# led-board.net
KiCad netlist of a schematic drawn in EAGLE
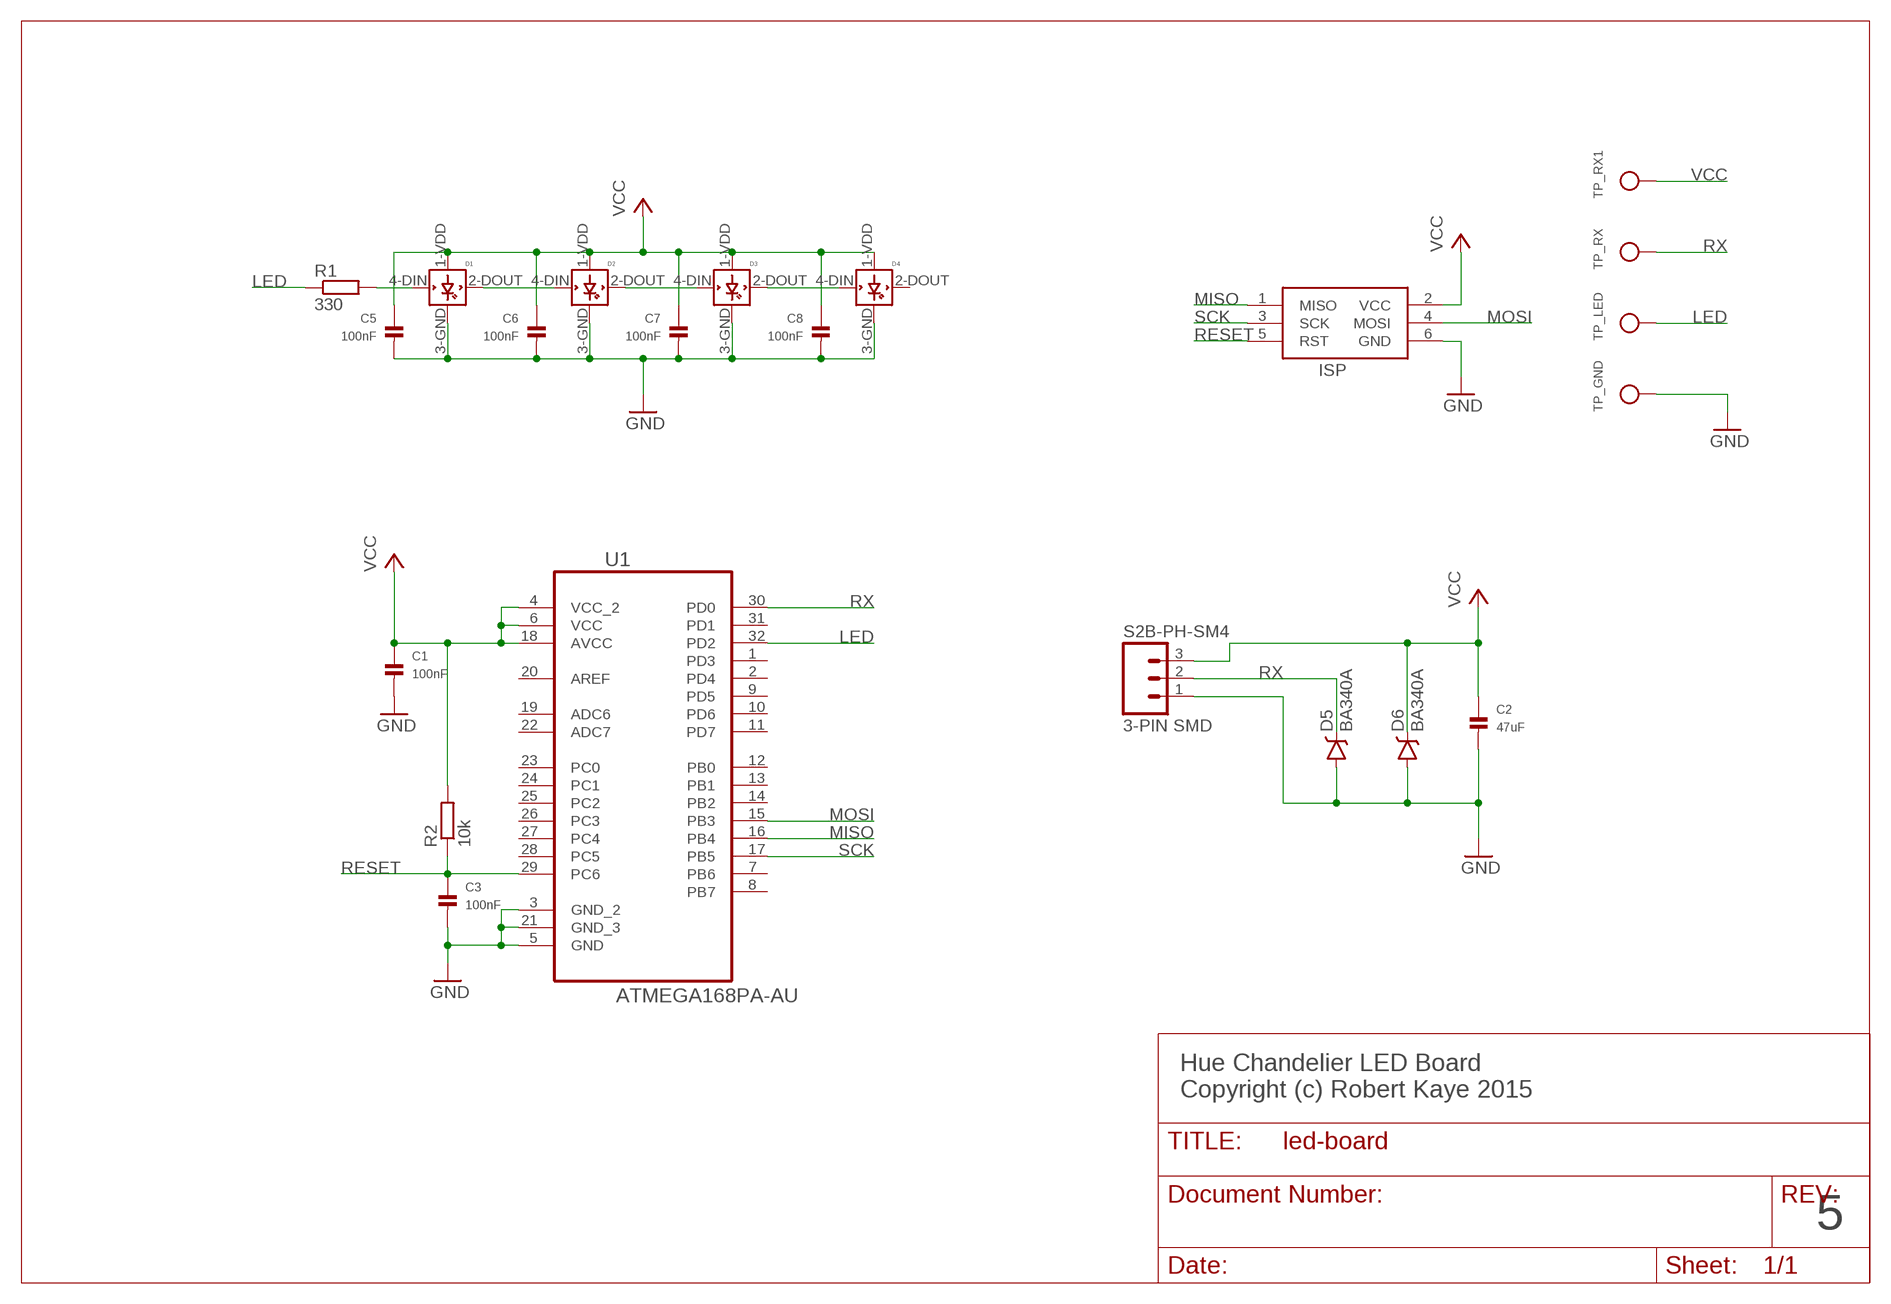
[diagram p0: schematic, sheet 1]

(export (version "E")
  (design (tool "Eeschema 10.0.6"))
  (components
    (comp (ref "C1")
      (value "100nF")
      (footprint "eagle-import:0805")
      (fields (field (name "MPN") "MCSH21B104K250CT"))
      (libsource (lib "eagle-import") (part "CAP_CERAMIC0805"))
    )
    (comp (ref "C2")
      (value "47uF")
      (footprint "eagle-import:1206")
      (fields (field (name "MPN") "CC0805KKX7R7BB105"))
      (libsource (lib "eagle-import") (part "CAP_CERAMIC1206"))
    )
    (comp (ref "C3")
      (value "100nF")
      (footprint "eagle-import:0805")
      (fields (field (name "MPN") "MCSH21B104K250CT"))
      (libsource (lib "eagle-import") (part "CAP_CERAMIC0805"))
    )
    (comp (ref "C5")
      (value "100nF")
      (footprint "eagle-import:0805")
      (fields (field (name "MPN") "MCSH21B104K250CT"))
      (libsource (lib "eagle-import") (part "CAP_CERAMIC0805"))
    )
    (comp (ref "C6")
      (value "100nF")
      (footprint "eagle-import:0805")
      (fields (field (name "MPN") "MCSH21B104K250CT"))
      (libsource (lib "eagle-import") (part "CAP_CERAMIC0805"))
    )
    (comp (ref "C7")
      (value "100nF")
      (footprint "eagle-import:0805")
      (fields (field (name "MPN") "MCSH21B104K250CT"))
      (libsource (lib "eagle-import") (part "CAP_CERAMIC0805"))
    )
    (comp (ref "C8")
      (value "100nF")
      (footprint "eagle-import:0805")
      (fields (field (name "MPN") "MCSH21B104K250CT"))
      (libsource (lib "eagle-import") (part "CAP_CERAMIC0805"))
    )
    (comp (ref "D1")
      (value "WS2812B")
      (footprint "eagle-import:WS2812B")
      (libsource (lib "eagle-import") (part "WS2812B"))
    )
    (comp (ref "D2")
      (value "WS2812B")
      (footprint "eagle-import:WS2812B")
      (libsource (lib "eagle-import") (part "WS2812B"))
    )
    (comp (ref "D3")
      (value "WS2812B")
      (footprint "eagle-import:WS2812B")
      (libsource (lib "eagle-import") (part "WS2812B"))
    )
    (comp (ref "D4")
      (value "WS2812B")
      (footprint "eagle-import:WS2812B")
      (libsource (lib "eagle-import") (part "WS2812B"))
    )
    (comp (ref "D5")
      (value "BA340A")
      (footprint "eagle-import:SMA-DIODE")
      (fields (field (name "MPN") "B330A-13-F"))
      (libsource (lib "eagle-import") (part "B340A"))
    )
    (comp (ref "D6")
      (value "BA340A")
      (footprint "eagle-import:SMA-DIODE")
      (fields (field (name "MPN") "B330A-13-F"))
      (libsource (lib "eagle-import") (part "B340A"))
    )
    (comp (ref "ISP")
      (value "AVRISP-6")
      (footprint "eagle-import:AVRISP")
      (libsource (lib "eagle-import") (part "AVRISP-6"))
    )
    (comp (ref "R1")
      (value "330")
      (footprint "eagle-import:R0805")
      (fields (field (name "MPN") "RC0805JR-07330RL"))
      (libsource (lib "eagle-import") (part "R-EU_R0805"))
    )
    (comp (ref "R2")
      (value "10k")
      (footprint "eagle-import:R0805")
      (fields (field (name "MPN") "RT0805FRE0710KL"))
      (libsource (lib "eagle-import") (part "R-EU_R0805"))
    )
    (comp (ref "S2B-PH-SM4")
      (value "3-PIN SMD")
      (footprint "eagle-import:JST-3-SMD")
      (fields (field (name "MF") "FARNELL") (field (name "MPN") "S3B-PH-SM4-TB(LF)(SN)"))
      (libsource (lib "eagle-import") (part "M03JST-SMD"))
    )
    (comp (ref "TP_GND")
      (value "TESTPOINT1.5X2.0MM_NOCREAM")
      (footprint "eagle-import:PAD-1.5X2.0")
      (libsource (lib "eagle-import") (part "TESTPOINT1.5X2.0MM_NOCREAM"))
    )
    (comp (ref "TP_LED")
      (value "TESTPOINT1.5X2.0MM_NOCREAM")
      (footprint "eagle-import:PAD-1.5X2.0")
      (libsource (lib "eagle-import") (part "TESTPOINT1.5X2.0MM_NOCREAM"))
    )
    (comp (ref "TP_RX")
      (value "TESTPOINT1.5X2.0MM_NOCREAM")
      (footprint "eagle-import:PAD-1.5X2.0")
      (libsource (lib "eagle-import") (part "TESTPOINT1.5X2.0MM_NOCREAM"))
    )
    (comp (ref "TP_RX1")
      (value "TESTPOINT1.5X2.0MM_NOCREAM")
      (footprint "eagle-import:PAD-1.5X2.0")
      (libsource (lib "eagle-import") (part "TESTPOINT1.5X2.0MM_NOCREAM"))
    )
    (comp (ref "U1")
      (value "ATMEGA168PA-AU")
      (footprint "eagle-import:QFP80P900X900X120-32N")
      (fields (field (name "OC_NEWARK") "68T2717"))
      (libsource (lib "eagle-import") (part "ATMEGA168PA-AU"))
    )
  )
  (nets
    (net (code "1") (name "/LED") (class "Default")
      (node (ref "R1") (pin "1") (pinfunction "1_1") (pintype "passive"))
      (node (ref "TP_LED") (pin "P$1") (pinfunction "P$1_P$1") (pintype "bidirectional"))
      (node (ref "U1") (pin "32") (pinfunction "PD2_32") (pintype "bidirectional"))
    )
    (net (code "2") (name "/MISO") (class "Default")
      (node (ref "ISP") (pin "1") (pinfunction "MISO_1") (pintype "input"))
      (node (ref "U1") (pin "16") (pinfunction "PB4_16") (pintype "bidirectional"))
    )
    (net (code "3") (name "/MOSI") (class "Default")
      (node (ref "ISP") (pin "4") (pinfunction "MOSI_4") (pintype "output"))
      (node (ref "U1") (pin "15") (pinfunction "PB3_15") (pintype "bidirectional"))
    )
    (net (code "4") (name "/RESET") (class "Default")
      (node (ref "C3") (pin "1") (pinfunction "P$1_1") (pintype "passive"))
      (node (ref "ISP") (pin "5") (pinfunction "RST_5") (pintype "output"))
      (node (ref "R2") (pin "1") (pinfunction "1_1") (pintype "passive"))
      (node (ref "U1") (pin "29") (pinfunction "PC6_29") (pintype "bidirectional"))
    )
    (net (code "5") (name "/RX") (class "Default")
      (node (ref "D5") (pin "C") (pinfunction "C_C") (pintype "passive"))
      (node (ref "S2B-PH-SM4") (pin "2") (pinfunction "2_2") (pintype "passive"))
      (node (ref "TP_RX") (pin "P$1") (pinfunction "P$1_P$1") (pintype "bidirectional"))
      (node (ref "U1") (pin "30") (pinfunction "PD0_30") (pintype "bidirectional"))
    )
    (net (code "6") (name "/SCK") (class "Default")
      (node (ref "ISP") (pin "3") (pinfunction "SCK_3") (pintype "output"))
      (node (ref "U1") (pin "17") (pinfunction "PB5_17") (pintype "bidirectional"))
    )
    (net (code "7") (name "GND") (class "Default")
      (node (ref "C1") (pin "2") (pinfunction "P$2_2") (pintype "passive"))
      (node (ref "C2") (pin "2") (pinfunction "P$2_2") (pintype "passive"))
      (node (ref "C3") (pin "2") (pinfunction "P$2_2") (pintype "passive"))
      (node (ref "C5") (pin "2") (pinfunction "P$2_2") (pintype "passive"))
      (node (ref "C6") (pin "2") (pinfunction "P$2_2") (pintype "passive"))
      (node (ref "C7") (pin "2") (pinfunction "P$2_2") (pintype "passive"))
      (node (ref "C8") (pin "2") (pinfunction "P$2_2") (pintype "passive"))
      (node (ref "D1") (pin "3-GND") (pinfunction "GND_3-GND") (pintype "bidirectional"))
      (node (ref "D2") (pin "3-GND") (pinfunction "GND_3-GND") (pintype "bidirectional"))
      (node (ref "D3") (pin "3-GND") (pinfunction "GND_3-GND") (pintype "bidirectional"))
      (node (ref "D4") (pin "3-GND") (pinfunction "GND_3-GND") (pintype "bidirectional"))
      (node (ref "D5") (pin "A") (pinfunction "A_A") (pintype "passive"))
      (node (ref "D6") (pin "A") (pinfunction "A_A") (pintype "passive"))
      (node (ref "ISP") (pin "6") (pinfunction "GND_6") (pintype "power_in"))
      (node (ref "S2B-PH-SM4") (pin "1") (pinfunction "1_1") (pintype "passive"))
      (node (ref "TP_GND") (pin "P$1") (pinfunction "P$1_P$1") (pintype "bidirectional"))
      (node (ref "U1") (pin "21") (pinfunction "GND_3_21") (pintype "passive"))
      (node (ref "U1") (pin "3") (pinfunction "GND_2_3") (pintype "passive"))
      (node (ref "U1") (pin "5") (pinfunction "GND_5") (pintype "passive"))
    )
    (net (code "8") (name "Net-(D1-DIN)") (class "Default")
      (node (ref "D1") (pin "4-DIN") (pinfunction "DIN_4-DIN") (pintype "input"))
      (node (ref "R1") (pin "2") (pinfunction "2_2") (pintype "passive"))
    )
    (net (code "9") (name "Net-(D1-DOUT)") (class "Default")
      (node (ref "D1") (pin "2-DOUT") (pinfunction "DOUT_2-DOUT") (pintype "output"))
      (node (ref "D2") (pin "4-DIN") (pinfunction "DIN_4-DIN") (pintype "input"))
    )
    (net (code "10") (name "Net-(D2-DOUT)") (class "Default")
      (node (ref "D2") (pin "2-DOUT") (pinfunction "DOUT_2-DOUT") (pintype "output"))
      (node (ref "D3") (pin "4-DIN") (pinfunction "DIN_4-DIN") (pintype "input"))
    )
    (net (code "11") (name "Net-(D3-DOUT)") (class "Default")
      (node (ref "D3") (pin "2-DOUT") (pinfunction "DOUT_2-DOUT") (pintype "output"))
      (node (ref "D4") (pin "4-DIN") (pinfunction "DIN_4-DIN") (pintype "input"))
    )
    (net (code "12") (name "VCC") (class "Default")
      (node (ref "C1") (pin "1") (pinfunction "P$1_1") (pintype "passive"))
      (node (ref "C2") (pin "1") (pinfunction "P$1_1") (pintype "passive"))
      (node (ref "C5") (pin "1") (pinfunction "P$1_1") (pintype "passive"))
      (node (ref "C6") (pin "1") (pinfunction "P$1_1") (pintype "passive"))
      (node (ref "C7") (pin "1") (pinfunction "P$1_1") (pintype "passive"))
      (node (ref "C8") (pin "1") (pinfunction "P$1_1") (pintype "passive"))
      (node (ref "D1") (pin "1-VDD") (pinfunction "VDD_1-VDD") (pintype "bidirectional"))
      (node (ref "D2") (pin "1-VDD") (pinfunction "VDD_1-VDD") (pintype "bidirectional"))
      (node (ref "D3") (pin "1-VDD") (pinfunction "VDD_1-VDD") (pintype "bidirectional"))
      (node (ref "D4") (pin "1-VDD") (pinfunction "VDD_1-VDD") (pintype "bidirectional"))
      (node (ref "D6") (pin "C") (pinfunction "C_C") (pintype "passive"))
      (node (ref "ISP") (pin "2") (pinfunction "VCC_2") (pintype "power_in"))
      (node (ref "R2") (pin "2") (pinfunction "2_2") (pintype "passive"))
      (node (ref "S2B-PH-SM4") (pin "3") (pinfunction "3_3") (pintype "passive"))
      (node (ref "TP_RX1") (pin "P$1") (pinfunction "P$1_P$1") (pintype "bidirectional"))
      (node (ref "U1") (pin "18") (pinfunction "AVCC_18") (pintype "power_in"))
      (node (ref "U1") (pin "4") (pinfunction "VCC_2_4") (pintype "power_in"))
      (node (ref "U1") (pin "6") (pinfunction "VCC_6") (pintype "power_in"))
    )
    (net (code "13") (name "unconnected-(D4-DOUT-Pad2-DOUT)") (class "Default")
      (node (ref "D4") (pin "2-DOUT") (pinfunction "DOUT_2-DOUT") (pintype "output"))
    )
    (net (code "14") (name "unconnected-(U1-ADC6-Pad19)") (class "Default")
      (node (ref "U1") (pin "19") (pinfunction "ADC6_19") (pintype "input"))
    )
    (net (code "15") (name "unconnected-(U1-ADC7-Pad22)") (class "Default")
      (node (ref "U1") (pin "22") (pinfunction "ADC7_22") (pintype "input"))
    )
    (net (code "16") (name "unconnected-(U1-AREF-Pad20)") (class "Default")
      (node (ref "U1") (pin "20") (pinfunction "AREF_20") (pintype "input"))
    )
    (net (code "17") (name "unconnected-(U1-PB0-Pad12)") (class "Default")
      (node (ref "U1") (pin "12") (pinfunction "PB0_12") (pintype "bidirectional"))
    )
    (net (code "18") (name "unconnected-(U1-PB1-Pad13)") (class "Default")
      (node (ref "U1") (pin "13") (pinfunction "PB1_13") (pintype "bidirectional"))
    )
    (net (code "19") (name "unconnected-(U1-PB2-Pad14)") (class "Default")
      (node (ref "U1") (pin "14") (pinfunction "PB2_14") (pintype "bidirectional"))
    )
    (net (code "20") (name "unconnected-(U1-PB6-Pad7)") (class "Default")
      (node (ref "U1") (pin "7") (pinfunction "PB6_7") (pintype "bidirectional"))
    )
    (net (code "21") (name "unconnected-(U1-PB7-Pad8)") (class "Default")
      (node (ref "U1") (pin "8") (pinfunction "PB7_8") (pintype "bidirectional"))
    )
    (net (code "22") (name "unconnected-(U1-PC0-Pad23)") (class "Default")
      (node (ref "U1") (pin "23") (pinfunction "PC0_23") (pintype "bidirectional"))
    )
    (net (code "23") (name "unconnected-(U1-PC1-Pad24)") (class "Default")
      (node (ref "U1") (pin "24") (pinfunction "PC1_24") (pintype "bidirectional"))
    )
    (net (code "24") (name "unconnected-(U1-PC2-Pad25)") (class "Default")
      (node (ref "U1") (pin "25") (pinfunction "PC2_25") (pintype "bidirectional"))
    )
    (net (code "25") (name "unconnected-(U1-PC3-Pad26)") (class "Default")
      (node (ref "U1") (pin "26") (pinfunction "PC3_26") (pintype "bidirectional"))
    )
    (net (code "26") (name "unconnected-(U1-PC4-Pad27)") (class "Default")
      (node (ref "U1") (pin "27") (pinfunction "PC4_27") (pintype "bidirectional"))
    )
    (net (code "27") (name "unconnected-(U1-PC5-Pad28)") (class "Default")
      (node (ref "U1") (pin "28") (pinfunction "PC5_28") (pintype "bidirectional"))
    )
    (net (code "28") (name "unconnected-(U1-PD1-Pad31)") (class "Default")
      (node (ref "U1") (pin "31") (pinfunction "PD1_31") (pintype "bidirectional"))
    )
    (net (code "29") (name "unconnected-(U1-PD3-Pad1)") (class "Default")
      (node (ref "U1") (pin "1") (pinfunction "PD3_1") (pintype "bidirectional"))
    )
    (net (code "30") (name "unconnected-(U1-PD4-Pad2)") (class "Default")
      (node (ref "U1") (pin "2") (pinfunction "PD4_2") (pintype "bidirectional"))
    )
    (net (code "31") (name "unconnected-(U1-PD5-Pad9)") (class "Default")
      (node (ref "U1") (pin "9") (pinfunction "PD5_9") (pintype "bidirectional"))
    )
    (net (code "32") (name "unconnected-(U1-PD6-Pad10)") (class "Default")
      (node (ref "U1") (pin "10") (pinfunction "PD6_10") (pintype "bidirectional"))
    )
    (net (code "33") (name "unconnected-(U1-PD7-Pad11)") (class "Default")
      (node (ref "U1") (pin "11") (pinfunction "PD7_11") (pintype "bidirectional"))
    )
  )
)
